# DP83848Ethernet.net
KiCad netlist of a schematic drawn in Altium Designer
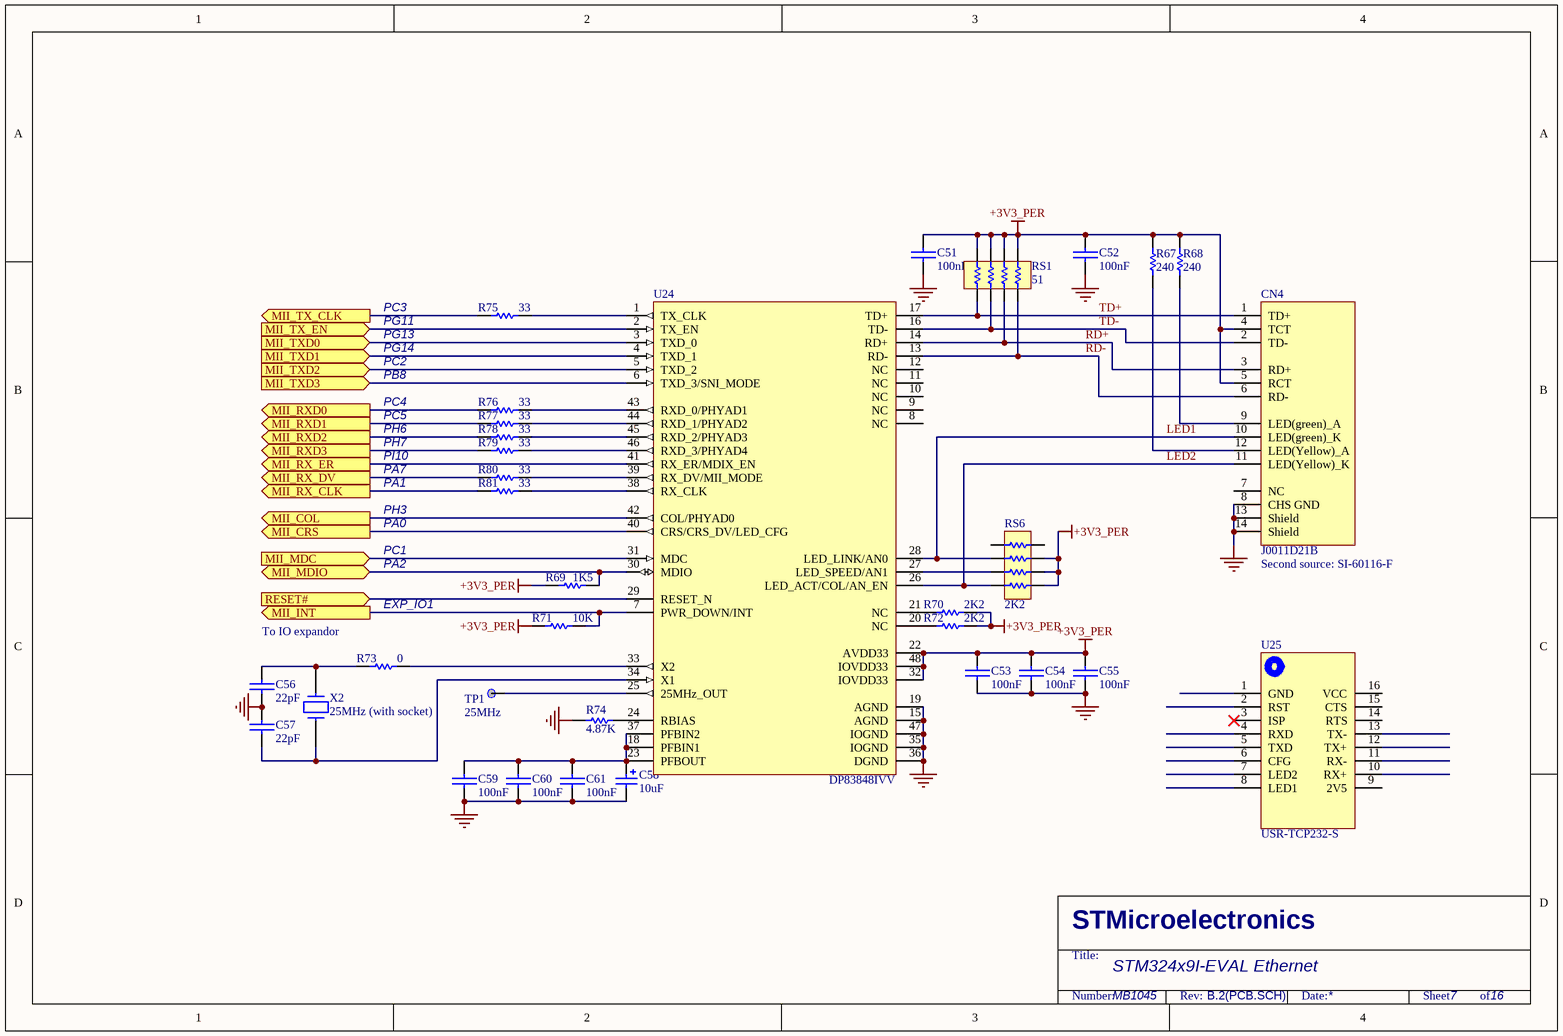
[diagram p0: DP83848Ethernet.SchDoc]

(export (version "E")
  (design (tool "Eeschema 10.0.6"))
  (components
    (comp (ref "C51")
      (value "100nF")
      (footprint "CAP_0603")
      (description "Capacitor")
      (libsource (lib "*") (part "CAP"))
    )
    (comp (ref "C52")
      (value "100nF")
      (footprint "CAP_0603")
      (description "Capacitor")
      (libsource (lib "*") (part "CAP"))
    )
    (comp (ref "C53")
      (value "100nF")
      (footprint "CAP_0603")
      (description "Capacitor")
      (libsource (lib "*") (part "CAP"))
    )
    (comp (ref "C54")
      (value "100nF")
      (footprint "CAP_0603")
      (description "Capacitor")
      (libsource (lib "*") (part "CAP"))
    )
    (comp (ref "C55")
      (value "100nF")
      (footprint "CAP_0603")
      (description "Capacitor")
      (libsource (lib "*") (part "CAP"))
    )
    (comp (ref "C56")
      (value "22pF")
      (footprint "CAP_0603")
      (description "Capacitor")
      (libsource (lib "*") (part "CAP"))
    )
    (comp (ref "C57")
      (value "22pF")
      (footprint "CAP_0603")
      (description "Capacitor")
      (libsource (lib "*") (part "CAP"))
    )
    (comp (ref "C58")
      (value "10uF")
      (footprint "CAP_TAN_A1206")
      (description "Polarized Capacitor (Radial)")
      (fields (field (name "PUBLISHER") "Altium Limited"))
      (libsource (lib "Miscellaneous Devices") (part "Cap Pol1"))
    )
    (comp (ref "C59")
      (value "100nF")
      (footprint "CAP_0603")
      (description "Capacitor")
      (libsource (lib "*") (part "CAP"))
    )
    (comp (ref "C60")
      (value "100nF")
      (footprint "CAP_0603")
      (description "Capacitor")
      (libsource (lib "*") (part "CAP"))
    )
    (comp (ref "C61")
      (value "100nF")
      (footprint "CAP_0603")
      (description "Capacitor")
      (libsource (lib "*") (part "CAP"))
    )
    (comp (ref "CN4") (value "J0011D21B") (footprint "RJ45") (libsource (lib "MB784") (part "J0011D21B")))
    (comp (ref "R67")
      (value "240")
      (footprint "RES_0603")
      (description "Resistor")
      (fields (field (name "PUBLISHER") "Altium Limited"))
      (libsource (lib "Miscellaneous Devices") (part "Res1"))
    )
    (comp (ref "R68")
      (value "240")
      (footprint "RES_0603")
      (description "Resistor")
      (fields (field (name "PUBLISHER") "Altium Limited"))
      (libsource (lib "Miscellaneous Devices") (part "Res1"))
    )
    (comp (ref "R69")
      (value "1K5")
      (footprint "RES_0603")
      (description "Resistor")
      (fields (field (name "PUBLISHER") "Altium Limited"))
      (libsource (lib "Miscellaneous Devices") (part "Res1"))
    )
    (comp (ref "R70")
      (value "2K2")
      (footprint "RES_0603")
      (description "Resistor")
      (fields (field (name "PUBLISHER") "Altium Limited"))
      (libsource (lib "Miscellaneous Devices") (part "Res1"))
    )
    (comp (ref "R71")
      (value "10K")
      (footprint "RES_0603")
      (description "Resistor")
      (fields (field (name "PUBLISHER") "Altium Limited"))
      (libsource (lib "Miscellaneous Devices") (part "Res1"))
    )
    (comp (ref "R72")
      (value "2K2")
      (footprint "RES_0603")
      (description "Resistor")
      (fields (field (name "PUBLISHER") "Altium Limited"))
      (libsource (lib "Miscellaneous Devices") (part "Res1"))
    )
    (comp (ref "R73")
      (value "0")
      (footprint "RES_0603")
      (description "Resistor")
      (fields (field (name "PUBLISHER") "Altium Limited"))
      (libsource (lib "Miscellaneous Devices") (part "Res1"))
    )
    (comp (ref "R74")
      (value "4.87K")
      (footprint "RES_0603")
      (description "Resistor")
      (fields (field (name "PUBLISHER") "Altium Limited"))
      (libsource (lib "Miscellaneous Devices") (part "Res1"))
    )
    (comp (ref "R75")
      (value "33")
      (footprint "RES_0603")
      (description "Resistor")
      (fields (field (name "PUBLISHER") "Altium Limited"))
      (libsource (lib "Miscellaneous Devices") (part "Res1"))
    )
    (comp (ref "R76")
      (value "33")
      (footprint "RES_0603")
      (description "Resistor")
      (fields (field (name "PUBLISHER") "Altium Limited"))
      (libsource (lib "Miscellaneous Devices") (part "Res1"))
    )
    (comp (ref "R77")
      (value "33")
      (footprint "RES_0603")
      (description "Resistor")
      (fields (field (name "PUBLISHER") "Altium Limited"))
      (libsource (lib "Miscellaneous Devices") (part "Res1"))
    )
    (comp (ref "R78")
      (value "33")
      (footprint "RES_0603")
      (description "Resistor")
      (fields (field (name "PUBLISHER") "Altium Limited"))
      (libsource (lib "Miscellaneous Devices") (part "Res1"))
    )
    (comp (ref "R79")
      (value "33")
      (footprint "RES_0603")
      (description "Resistor")
      (fields (field (name "PUBLISHER") "Altium Limited"))
      (libsource (lib "Miscellaneous Devices") (part "Res1"))
    )
    (comp (ref "R80")
      (value "33")
      (footprint "RES_0603")
      (description "Resistor")
      (fields (field (name "PUBLISHER") "Altium Limited"))
      (libsource (lib "Miscellaneous Devices") (part "Res1"))
    )
    (comp (ref "R81")
      (value "33")
      (footprint "RES_0603")
      (description "Resistor")
      (fields (field (name "PUBLISHER") "Altium Limited"))
      (libsource (lib "Miscellaneous Devices") (part "Res1"))
    )
    (comp (ref "RS1")
      (value "51")
      (footprint "LC-0603_Rx4")
      (libsource (lib "MB784") (part "Resister Array"))
    )
    (comp (ref "RS6") (value "2K2") (footprint "LC-0603_Rx4") (libsource (lib "") (part "Resister Array_1")))
    (comp (ref "TP1") (value "25MHz") (footprint "TP") (libsource (lib "*") (part "TP")))
    (comp (ref "U24")
      (value "DP83848IVV")
      (footprint "LC-LQFP-48_7x7x05P")
      (libsource (lib "MB784") (part "DP83848CVV"))
    )
    (comp (ref "U25")
      (value "USR-TCP232-S")
      (footprint "USR-TCP232-S")
      (libsource (lib "USR-TCP232-S2-SCH") (part "USR-TCP232-S"))
    )
    (comp (ref "X2")
      (value "25MHz (with socket)")
      (footprint "OSC-YSX-3225_4P")
      (description "Crystal")
      (libsource (lib "*") (part "CRYSTAL"))
    )
  )
  (nets
    (net (code "1") (name "+3V3_PER") (class "Default")
      (node (ref "C51") (pin "2") (pinfunction "2_2") (pintype "passive"))
      (node (ref "C52") (pin "2") (pinfunction "2_2") (pintype "passive"))
      (node (ref "C53") (pin "1") (pinfunction "1_1") (pintype "passive"))
      (node (ref "C54") (pin "2") (pinfunction "2_2") (pintype "passive"))
      (node (ref "C55") (pin "2") (pinfunction "2_2") (pintype "passive"))
      (node (ref "CN4") (pin "4") (pinfunction "TCT_4") (pintype "passive"))
      (node (ref "CN4") (pin "5") (pinfunction "RCT_5") (pintype "passive"))
      (node (ref "R67") (pin "2") (pinfunction "2_2") (pintype "passive"))
      (node (ref "R68") (pin "2") (pinfunction "2_2") (pintype "passive"))
      (node (ref "R69") (pin "2") (pinfunction "2_2") (pintype "passive"))
      (node (ref "R70") (pin "2") (pinfunction "2_2") (pintype "passive"))
      (node (ref "R71") (pin "1") (pinfunction "1_1") (pintype "passive"))
      (node (ref "R72") (pin "2") (pinfunction "2_2") (pintype "passive"))
      (node (ref "RS1") (pin "2") (pinfunction "2_2") (pintype "passive"))
      (node (ref "RS1") (pin "4") (pinfunction "4_4") (pintype "passive"))
      (node (ref "RS1") (pin "6") (pinfunction "6_6") (pintype "passive"))
      (node (ref "RS1") (pin "8") (pinfunction "8_8") (pintype "passive"))
      (node (ref "RS6") (pin "1") (pinfunction "1_1") (pintype "passive"))
      (node (ref "RS6") (pin "3") (pinfunction "3_3") (pintype "passive"))
      (node (ref "RS6") (pin "5") (pinfunction "5_5") (pintype "passive"))
      (node (ref "U24") (pin "22") (pinfunction "AVDD33_22") (pintype "passive"))
      (node (ref "U24") (pin "32") (pinfunction "IOVDD33_32") (pintype "passive"))
      (node (ref "U24") (pin "48") (pinfunction "IOVDD33_48") (pintype "passive"))
    )
    (net (code "2") (name "/LED1") (class "Default")
      (node (ref "CN4") (pin "10") (pinfunction "LED(green)_K_10") (pintype "passive"))
      (node (ref "RS6") (pin "6") (pinfunction "6_6") (pintype "passive"))
      (node (ref "U24") (pin "28") (pinfunction "LED_LINK/AN0_28") (pintype "passive"))
    )
    (net (code "3") (name "/LED2") (class "Default")
      (node (ref "CN4") (pin "11") (pinfunction "LED(Yellow)_K_11") (pintype "passive"))
      (node (ref "RS6") (pin "2") (pinfunction "2_2") (pintype "passive"))
      (node (ref "U24") (pin "26") (pinfunction "LED_ACT/COL/AN_EN_26") (pintype "passive"))
    )
    (net (code "4") (name "/MII_COL") (class "Default")
      (node (ref "U24") (pin "42") (pinfunction "COL/PHYAD0_42") (pintype "output"))
    )
    (net (code "5") (name "/MII_CRS") (class "Default")
      (node (ref "U24") (pin "40") (pinfunction "CRS/CRS_DV/LED_CFG_40") (pintype "output"))
    )
    (net (code "6") (name "/MII_INT") (class "Default")
      (node (ref "R71") (pin "2") (pinfunction "2_2") (pintype "passive"))
      (node (ref "U24") (pin "7") (pinfunction "PWR_DOWN/INT_7") (pintype "passive"))
    )
    (net (code "7") (name "/MII_MDC") (class "Default")
      (node (ref "U24") (pin "31") (pinfunction "MDC_31") (pintype "input"))
    )
    (net (code "8") (name "/MII_MDIO") (class "Default")
      (node (ref "R69") (pin "1") (pinfunction "1_1") (pintype "passive"))
      (node (ref "U24") (pin "30") (pinfunction "MDIO_30") (pintype "bidirectional"))
    )
    (net (code "9") (name "/MII_RXD0") (class "Default")
      (node (ref "R76") (pin "2") (pinfunction "2_2") (pintype "passive"))
    )
    (net (code "10") (name "/MII_RXD1") (class "Default")
      (node (ref "R77") (pin "2") (pinfunction "2_2") (pintype "passive"))
    )
    (net (code "11") (name "/MII_RXD2") (class "Default")
      (node (ref "R78") (pin "2") (pinfunction "2_2") (pintype "passive"))
    )
    (net (code "12") (name "/MII_RXD3") (class "Default")
      (node (ref "R79") (pin "2") (pinfunction "2_2") (pintype "passive"))
    )
    (net (code "13") (name "/MII_RX_CLK") (class "Default")
      (node (ref "R81") (pin "2") (pinfunction "2_2") (pintype "passive"))
    )
    (net (code "14") (name "/MII_RX_DV") (class "Default")
      (node (ref "R80") (pin "2") (pinfunction "2_2") (pintype "passive"))
    )
    (net (code "15") (name "/MII_RX_ER") (class "Default")
      (node (ref "U24") (pin "41") (pinfunction "RX_ER/MDIX_EN_41") (pintype "output"))
    )
    (net (code "16") (name "/MII_TXD0") (class "Default")
      (node (ref "U24") (pin "3") (pinfunction "TXD_0_3") (pintype "input"))
    )
    (net (code "17") (name "/MII_TXD1") (class "Default")
      (node (ref "U24") (pin "4") (pinfunction "TXD_1_4") (pintype "input"))
    )
    (net (code "18") (name "/MII_TXD2") (class "Default")
      (node (ref "U24") (pin "5") (pinfunction "TXD_2_5") (pintype "input"))
    )
    (net (code "19") (name "/MII_TXD3") (class "Default")
      (node (ref "U24") (pin "6") (pinfunction "TXD_3/SNI_MODE_6") (pintype "input"))
    )
    (net (code "20") (name "/MII_TX_CLK") (class "Default")
      (node (ref "R75") (pin "2") (pinfunction "2_2") (pintype "passive"))
    )
    (net (code "21") (name "/MII_TX_EN") (class "Default")
      (node (ref "U24") (pin "2") (pinfunction "TX_EN_2") (pintype "input"))
    )
    (net (code "22") (name "/RD+") (class "Default")
      (node (ref "CN4") (pin "3") (pinfunction "RD+_3") (pintype "passive"))
      (node (ref "RS1") (pin "5") (pinfunction "5_5") (pintype "passive"))
      (node (ref "U24") (pin "14") (pinfunction "RD+_14") (pintype "passive"))
    )
    (net (code "23") (name "/RD-") (class "Default")
      (node (ref "CN4") (pin "6") (pinfunction "RD-_6") (pintype "passive"))
      (node (ref "RS1") (pin "7") (pinfunction "7_7") (pintype "passive"))
      (node (ref "U24") (pin "13") (pinfunction "RD-_13") (pintype "passive"))
    )
    (net (code "24") (name "/RESET#") (class "Default")
      (node (ref "U24") (pin "29") (pinfunction "RESET_N_29") (pintype "passive"))
    )
    (net (code "25") (name "/TD+") (class "Default")
      (node (ref "CN4") (pin "1") (pinfunction "TD+_1") (pintype "passive"))
      (node (ref "RS1") (pin "1") (pinfunction "1_1") (pintype "passive"))
      (node (ref "U24") (pin "17") (pinfunction "TD+_17") (pintype "passive"))
    )
    (net (code "26") (name "/TD-") (class "Default")
      (node (ref "CN4") (pin "2") (pinfunction "TD-_2") (pintype "passive"))
      (node (ref "RS1") (pin "3") (pinfunction "3_3") (pintype "passive"))
      (node (ref "U24") (pin "16") (pinfunction "TD-_16") (pintype "passive"))
    )
    (net (code "27") (name "GND") (class "Default")
      (node (ref "C51") (pin "1") (pinfunction "1_1") (pintype "passive"))
      (node (ref "C52") (pin "1") (pinfunction "1_1") (pintype "passive"))
      (node (ref "C53") (pin "2") (pinfunction "2_2") (pintype "passive"))
      (node (ref "C54") (pin "1") (pinfunction "1_1") (pintype "passive"))
      (node (ref "C55") (pin "1") (pinfunction "1_1") (pintype "passive"))
      (node (ref "C56") (pin "1") (pinfunction "1_1") (pintype "passive"))
      (node (ref "C57") (pin "2") (pinfunction "2_2") (pintype "passive"))
      (node (ref "C58") (pin "2") (pinfunction "2_2") (pintype "passive"))
      (node (ref "C59") (pin "2") (pinfunction "2_2") (pintype "passive"))
      (node (ref "C60") (pin "1") (pinfunction "1_1") (pintype "passive"))
      (node (ref "C61") (pin "1") (pinfunction "1_1") (pintype "passive"))
      (node (ref "CN4") (pin "13") (pinfunction "Shield_13") (pintype "passive"))
      (node (ref "CN4") (pin "14") (pinfunction "Shield_14") (pintype "passive"))
      (node (ref "CN4") (pin "8") (pinfunction "CHS_GND_8") (pintype "passive"))
      (node (ref "R74") (pin "1") (pinfunction "1_1") (pintype "passive"))
      (node (ref "U24") (pin "15") (pinfunction "AGND_15") (pintype "passive"))
      (node (ref "U24") (pin "19") (pinfunction "AGND_19") (pintype "passive"))
      (node (ref "U24") (pin "35") (pinfunction "IOGND_35") (pintype "passive"))
      (node (ref "U24") (pin "36") (pinfunction "DGND_36") (pintype "passive"))
      (node (ref "U24") (pin "47") (pinfunction "IOGND_47") (pintype "passive"))
    )
    (net (code "28") (name "Net-(C56-Pad2)") (class "Default")
      (node (ref "C56") (pin "2") (pinfunction "2_2") (pintype "passive"))
      (node (ref "R73") (pin "2") (pinfunction "2_2") (pintype "passive"))
      (node (ref "X2") (pin "2") (pinfunction "2_2") (pintype "passive"))
    )
    (net (code "29") (name "Net-(CN4-LED(Yellow)_A)") (class "Default")
      (node (ref "CN4") (pin "12") (pinfunction "LED(Yellow)_A_12") (pintype "passive"))
      (node (ref "R67") (pin "1") (pinfunction "1_1") (pintype "passive"))
    )
    (net (code "30") (name "Net-(CN4-LED(green)_A)") (class "Default")
      (node (ref "CN4") (pin "9") (pinfunction "LED(green)_A_9") (pintype "passive"))
      (node (ref "R68") (pin "1") (pinfunction "1_1") (pintype "passive"))
    )
    (net (code "31") (name "Net-(R70-Pad1)") (class "Default")
      (node (ref "R70") (pin "1") (pinfunction "1_1") (pintype "passive"))
      (node (ref "U24") (pin "21") (pinfunction "NC_21") (pintype "passive"))
    )
    (net (code "32") (name "Net-(R72-Pad1)") (class "Default")
      (node (ref "R72") (pin "1") (pinfunction "1_1") (pintype "passive"))
      (node (ref "U24") (pin "20") (pinfunction "NC_20") (pintype "passive"))
    )
    (net (code "33") (name "Net-(U24-25MHz_OUT)") (class "Default")
      (node (ref "TP1") (pin "1") (pinfunction "1_1") (pintype "passive"))
      (node (ref "U24") (pin "25") (pinfunction "25MHz_OUT_25") (pintype "output"))
    )
    (net (code "34") (name "Net-(U24-LED_SPEED{slash}AN1)") (class "Default")
      (node (ref "RS6") (pin "4") (pinfunction "4_4") (pintype "passive"))
      (node (ref "U24") (pin "27") (pinfunction "LED_SPEED/AN1_27") (pintype "passive"))
    )
    (net (code "35") (name "Net-(U24-PFBIN1)") (class "Default")
      (node (ref "C58") (pin "1") (pinfunction "1_1") (pintype "passive"))
      (node (ref "C59") (pin "1") (pinfunction "1_1") (pintype "passive"))
      (node (ref "C60") (pin "2") (pinfunction "2_2") (pintype "passive"))
      (node (ref "C61") (pin "2") (pinfunction "2_2") (pintype "passive"))
      (node (ref "U24") (pin "18") (pinfunction "PFBIN1_18") (pintype "passive"))
      (node (ref "U24") (pin "23") (pinfunction "PFBOUT_23") (pintype "passive"))
      (node (ref "U24") (pin "37") (pinfunction "PFBIN2_37") (pintype "passive"))
    )
    (net (code "36") (name "Net-(U24-RBIAS)") (class "Default")
      (node (ref "R74") (pin "2") (pinfunction "2_2") (pintype "passive"))
      (node (ref "U24") (pin "24") (pinfunction "RBIAS_24") (pintype "passive"))
    )
    (net (code "37") (name "Net-(U24-RXD_0{slash}PHYAD1)") (class "Default")
      (node (ref "R76") (pin "1") (pinfunction "1_1") (pintype "passive"))
      (node (ref "U24") (pin "43") (pinfunction "RXD_0/PHYAD1_43") (pintype "output"))
    )
    (net (code "38") (name "Net-(U24-RXD_1{slash}PHYAD2)") (class "Default")
      (node (ref "R77") (pin "1") (pinfunction "1_1") (pintype "passive"))
      (node (ref "U24") (pin "44") (pinfunction "RXD_1/PHYAD2_44") (pintype "output"))
    )
    (net (code "39") (name "Net-(U24-RXD_2{slash}PHYAD3)") (class "Default")
      (node (ref "R78") (pin "1") (pinfunction "1_1") (pintype "passive"))
      (node (ref "U24") (pin "45") (pinfunction "RXD_2/PHYAD3_45") (pintype "output"))
    )
    (net (code "40") (name "Net-(U24-RXD_3{slash}PHYAD4)") (class "Default")
      (node (ref "R79") (pin "1") (pinfunction "1_1") (pintype "passive"))
      (node (ref "U24") (pin "46") (pinfunction "RXD_3/PHYAD4_46") (pintype "output"))
    )
    (net (code "41") (name "Net-(U24-RX_CLK)") (class "Default")
      (node (ref "R81") (pin "1") (pinfunction "1_1") (pintype "passive"))
      (node (ref "U24") (pin "38") (pinfunction "RX_CLK_38") (pintype "output"))
    )
    (net (code "42") (name "Net-(U24-RX_DV{slash}MII_MODE)") (class "Default")
      (node (ref "R80") (pin "1") (pinfunction "1_1") (pintype "passive"))
      (node (ref "U24") (pin "39") (pinfunction "RX_DV/MII_MODE_39") (pintype "output"))
    )
    (net (code "43") (name "Net-(U24-TX_CLK)") (class "Default")
      (node (ref "R75") (pin "1") (pinfunction "1_1") (pintype "passive"))
      (node (ref "U24") (pin "1") (pinfunction "TX_CLK_1") (pintype "output"))
    )
    (net (code "44") (name "Net-(U24-X1)") (class "Default")
      (node (ref "C57") (pin "1") (pinfunction "1_1") (pintype "passive"))
      (node (ref "U24") (pin "34") (pinfunction "X1_34") (pintype "input"))
      (node (ref "X2") (pin "1") (pinfunction "1_1") (pintype "passive"))
    )
    (net (code "45") (name "Net-(U24-X2)") (class "Default")
      (node (ref "R73") (pin "1") (pinfunction "1_1") (pintype "passive"))
      (node (ref "U24") (pin "33") (pinfunction "X2_33") (pintype "output"))
    )
    (net (code "46") (name "unconnected-(CN4-NC-Pad7)") (class "Default")
      (node (ref "CN4") (pin "7") (pinfunction "NC_7") (pintype "passive"))
    )
    (net (code "47") (name "unconnected-(RS6-Pad7)") (class "Default")
      (node (ref "RS6") (pin "7") (pinfunction "7_7") (pintype "passive"))
    )
    (net (code "48") (name "unconnected-(RS6-Pad8)") (class "Default")
      (node (ref "RS6") (pin "8") (pinfunction "8_8") (pintype "passive"))
    )
    (net (code "49") (name "unconnected-(U24-NC-Pad8)") (class "Default")
      (node (ref "U24") (pin "8") (pinfunction "NC_8") (pintype "passive"))
    )
    (net (code "50") (name "unconnected-(U24-NC-Pad9)") (class "Default")
      (node (ref "U24") (pin "9") (pinfunction "NC_9") (pintype "passive"))
    )
    (net (code "51") (name "unconnected-(U24-NC-Pad10)") (class "Default")
      (node (ref "U24") (pin "10") (pinfunction "NC_10") (pintype "passive"))
    )
    (net (code "52") (name "unconnected-(U24-NC-Pad11)") (class "Default")
      (node (ref "U24") (pin "11") (pinfunction "NC_11") (pintype "passive"))
    )
    (net (code "53") (name "unconnected-(U24-NC-Pad12)") (class "Default")
      (node (ref "U24") (pin "12") (pinfunction "NC_12") (pintype "passive"))
    )
    (net (code "54") (name "unconnected-(U25-2V5-Pad9)") (class "Default")
      (node (ref "U25") (pin "9") (pinfunction "2V5_9") (pintype "passive"))
    )
    (net (code "55") (name "unconnected-(U25-CFG-Pad6)") (class "Default")
      (node (ref "U25") (pin "6") (pinfunction "CFG_6") (pintype "passive"))
    )
    (net (code "56") (name "unconnected-(U25-CTS-Pad15)") (class "Default")
      (node (ref "U25") (pin "15") (pinfunction "CTS_15") (pintype "passive"))
    )
    (net (code "57") (name "unconnected-(U25-GND-Pad1)") (class "Default")
      (node (ref "U25") (pin "1") (pinfunction "GND_1") (pintype "passive"))
    )
    (net (code "58") (name "unconnected-(U25-ISP-Pad3)") (class "Default")
      (node (ref "U25") (pin "3") (pinfunction "ISP_3") (pintype "passive+no_connect"))
    )
    (net (code "59") (name "unconnected-(U25-LED1-Pad8)") (class "Default")
      (node (ref "U25") (pin "8") (pinfunction "LED1_8") (pintype "passive"))
    )
    (net (code "60") (name "unconnected-(U25-LED2-Pad7)") (class "Default")
      (node (ref "U25") (pin "7") (pinfunction "LED2_7") (pintype "passive"))
    )
    (net (code "61") (name "unconnected-(U25-RST-Pad2)") (class "Default")
      (node (ref "U25") (pin "2") (pinfunction "RST_2") (pintype "passive"))
    )
    (net (code "62") (name "unconnected-(U25-RTS-Pad14)") (class "Default")
      (node (ref "U25") (pin "14") (pinfunction "RTS_14") (pintype "passive"))
    )
    (net (code "63") (name "unconnected-(U25-RX+-Pad10)") (class "Default")
      (node (ref "U25") (pin "10") (pinfunction "RX+_10") (pintype "passive"))
    )
    (net (code "64") (name "unconnected-(U25-RX--Pad11)") (class "Default")
      (node (ref "U25") (pin "11") (pinfunction "RX-_11") (pintype "passive"))
    )
    (net (code "65") (name "unconnected-(U25-RXD-Pad4)") (class "Default")
      (node (ref "U25") (pin "4") (pinfunction "RXD_4") (pintype "passive"))
    )
    (net (code "66") (name "unconnected-(U25-TX+-Pad12)") (class "Default")
      (node (ref "U25") (pin "12") (pinfunction "TX+_12") (pintype "passive"))
    )
    (net (code "67") (name "unconnected-(U25-TX--Pad13)") (class "Default")
      (node (ref "U25") (pin "13") (pinfunction "TX-_13") (pintype "passive"))
    )
    (net (code "68") (name "unconnected-(U25-TXD-Pad5)") (class "Default")
      (node (ref "U25") (pin "5") (pinfunction "TXD_5") (pintype "passive"))
    )
    (net (code "69") (name "unconnected-(U25-VCC-Pad16)") (class "Default")
      (node (ref "U25") (pin "16") (pinfunction "VCC_16") (pintype "passive"))
    )
  )
)
